# Ethernet.net
KiCad netlist of a schematic drawn in Altium Designer
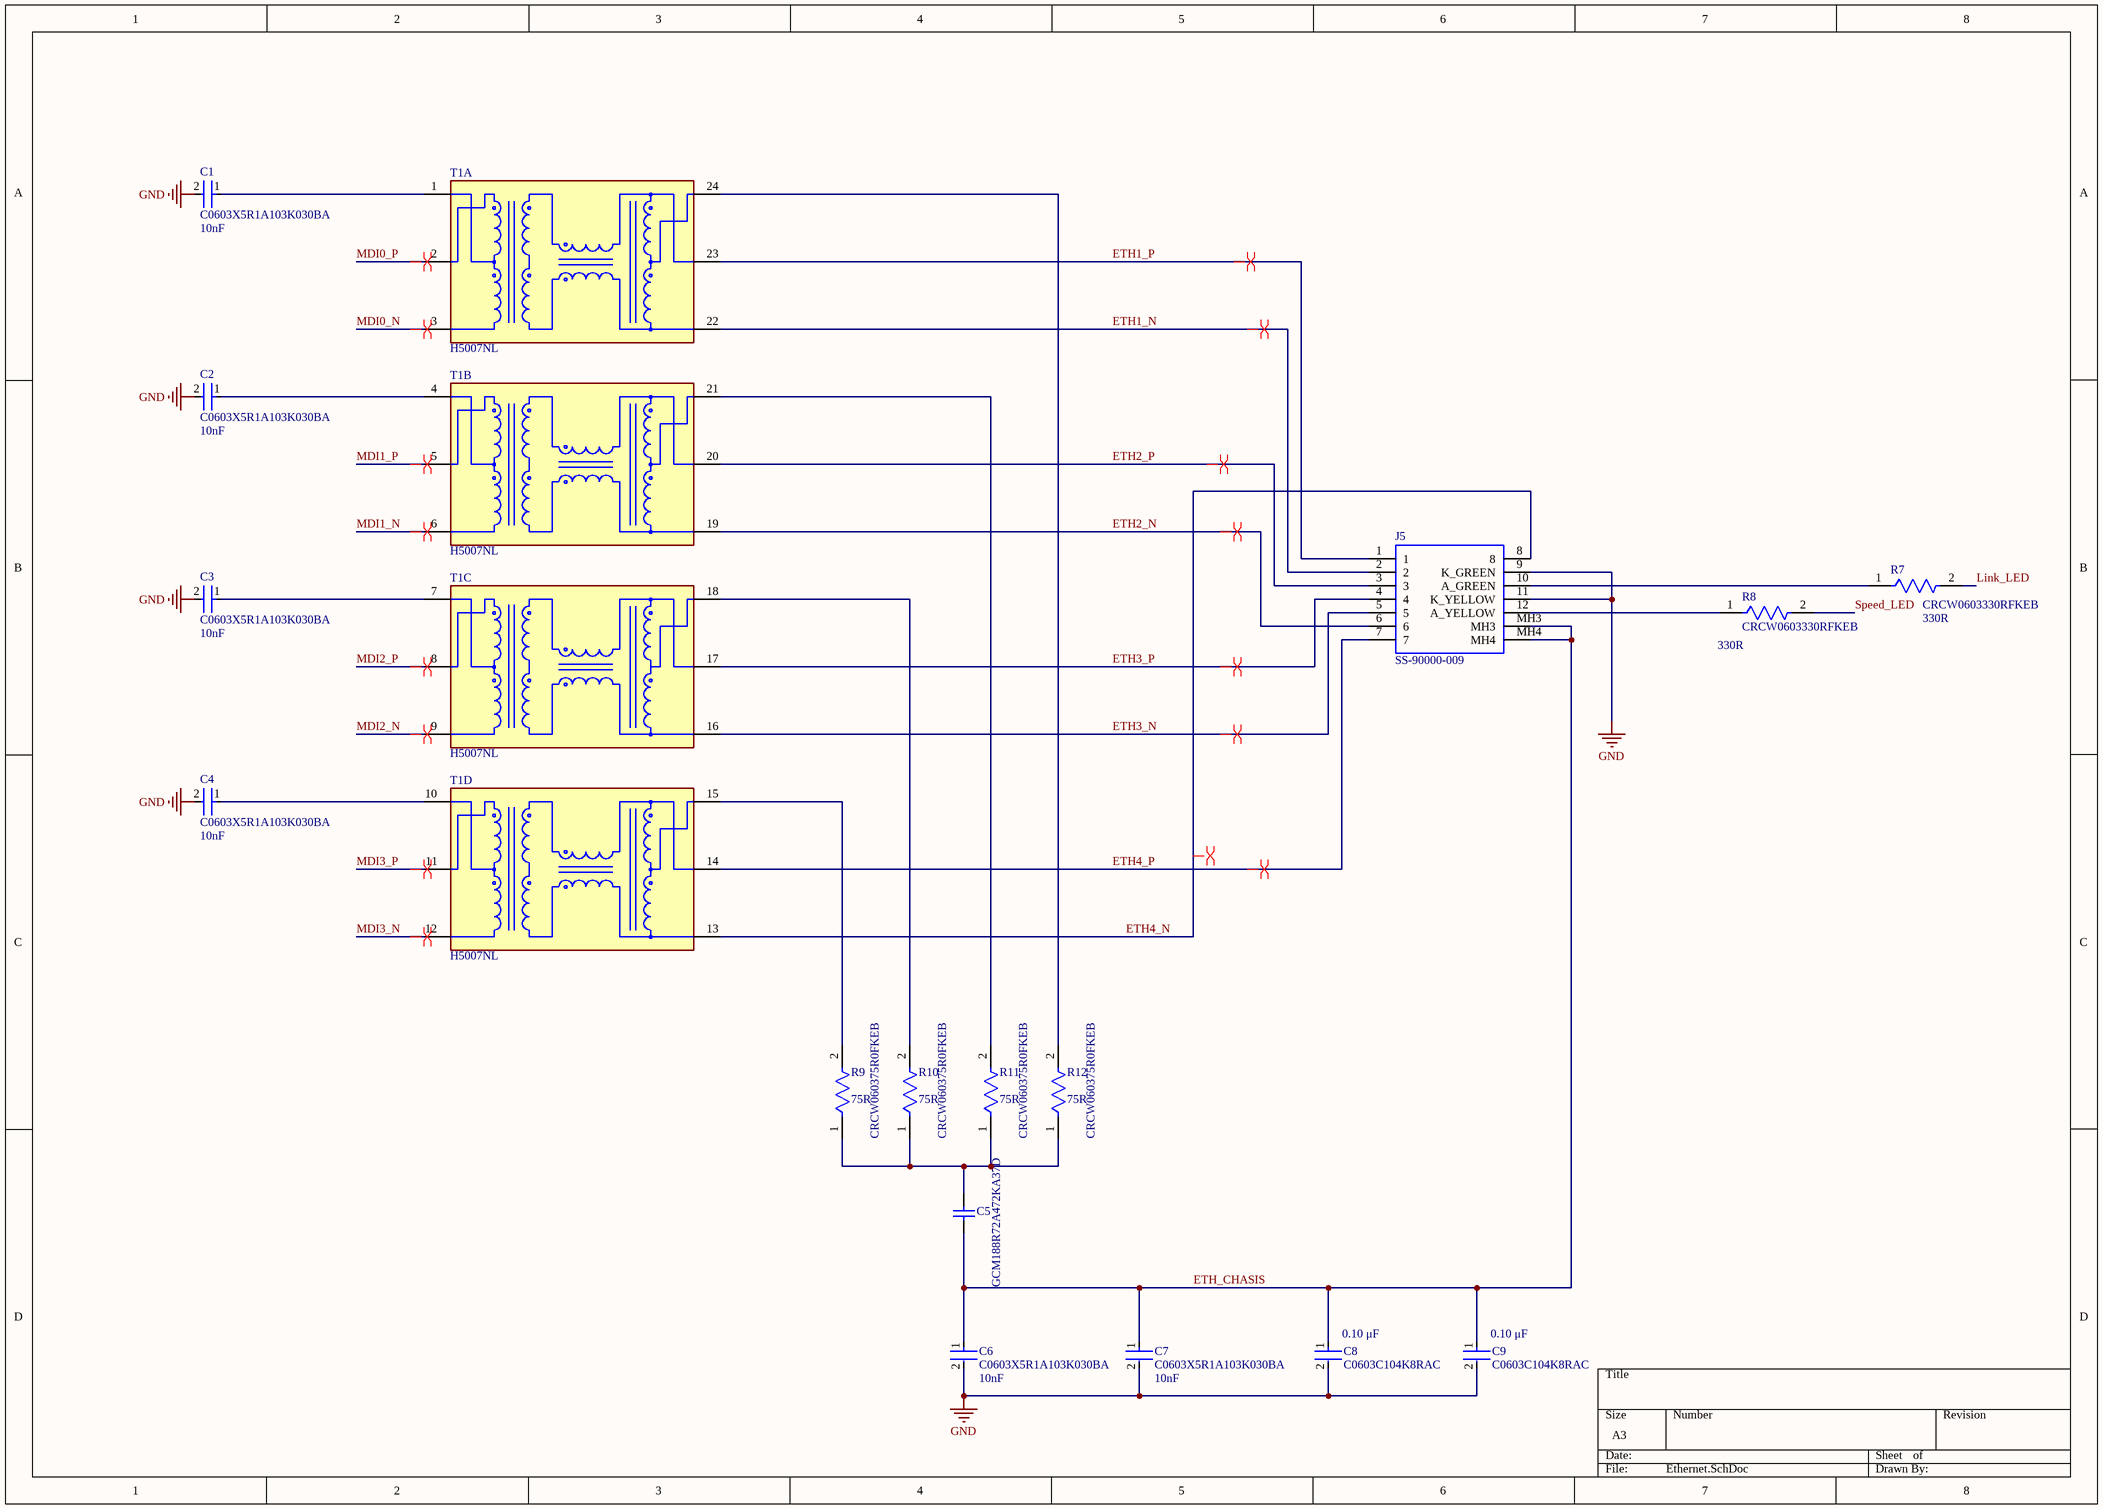
[diagram p0: Ethernet.SchDoc]

(export (version "E")
  (design (tool "Eeschema 10.0.6"))
  (components
    (comp (ref "C1")
      (value "C0603X5R1A103K030BA")
      (footprint "FP-C0603-030-0_03-MFG")
      (description "Multilayer Ceramic Capacitors 10nF ±10% 10V X5R SMD 0201")
      (fields
        (field (name "CAPACITANCE") "10nF")
        (field (name "TOLERANCE") "10%")
        (field (name "VOLTAGE") "10V")
      )
      (libsource (lib "Altium Content Vault") (part "02cd4be3c70576c341d710602a673aa"))
    )
    (comp (ref "C2")
      (value "C0603X5R1A103K030BA")
      (footprint "FP-C0603-030-0_03-MFG")
      (description "Multilayer Ceramic Capacitors 10nF ±10% 10V X5R SMD 0201")
      (fields
        (field (name "CAPACITANCE") "10nF")
        (field (name "TOLERANCE") "10%")
        (field (name "VOLTAGE") "10V")
      )
      (libsource (lib "Altium Content Vault") (part "02cd4be3c70576c341d710602a673aa"))
    )
    (comp (ref "C3")
      (value "C0603X5R1A103K030BA")
      (footprint "FP-C0603-030-0_03-MFG")
      (description "Multilayer Ceramic Capacitors 10nF ±10% 10V X5R SMD 0201")
      (fields
        (field (name "CAPACITANCE") "10nF")
        (field (name "TOLERANCE") "10%")
        (field (name "VOLTAGE") "10V")
      )
      (libsource (lib "Altium Content Vault") (part "02cd4be3c70576c341d710602a673aa"))
    )
    (comp (ref "C4")
      (value "C0603X5R1A103K030BA")
      (footprint "FP-C0603-030-0_03-MFG")
      (description "Multilayer Ceramic Capacitors 10nF ±10% 10V X5R SMD 0201")
      (fields
        (field (name "CAPACITANCE") "10nF")
        (field (name "TOLERANCE") "10%")
        (field (name "VOLTAGE") "10V")
      )
      (libsource (lib "Altium Content Vault") (part "02cd4be3c70576c341d710602a673aa"))
    )
    (comp (ref "C5")
      (value "GCM188R72A472KA37D")
      (footprint "CAPC1608X90X35ML10T15")
      (fields (field (name "MANUFACTURER") "Murata"))
      (libsource (lib "Altium Content Vault") (part "CAP"))
    )
    (comp (ref "C6")
      (value "C0603X5R1A103K030BA")
      (footprint "FP-C0603-030-0_03-MFG")
      (description "Multilayer Ceramic Capacitors 10nF ±10% 10V X5R SMD 0201")
      (fields
        (field (name "CAPACITANCE") "10nF")
        (field (name "TOLERANCE") "10%")
        (field (name "VOLTAGE") "10V")
      )
      (libsource (lib "Altium Content Vault") (part "02cd4be3c70576c341d710602a673aa"))
    )
    (comp (ref "C7")
      (value "C0603X5R1A103K030BA")
      (footprint "FP-C0603-030-0_03-MFG")
      (description "Multilayer Ceramic Capacitors 10nF ±10% 10V X5R SMD 0201")
      (fields
        (field (name "CAPACITANCE") "10nF")
        (field (name "TOLERANCE") "10%")
        (field (name "VOLTAGE") "10V")
      )
      (libsource (lib "Altium Content Vault") (part "02cd4be3c70576c341d710602a673aa"))
    )
    (comp (ref "C8")
      (value "C0603C104K8RAC")
      (footprint "FP-C0603C-CF-MFG")
      (description "C0603 0.10 μF X7R 30ppm/°C 10.00% 10 V")
      (fields
        (field (name "MANUFACTURER") "KEMET")
        (field (name "CAPACITANCE") "0.10 μF")
        (field (name "OCTOPART") "https://octopart.com/c0603c104k8rac-kemet-1325403")
      )
      (libsource (lib "Altium Content Vault") (part "b4654b650e69147ec39a6b967a45e02"))
    )
    (comp (ref "C9")
      (value "C0603C104K8RAC")
      (footprint "FP-C0603C-CF-MFG")
      (description "C0603 0.10 μF X7R 30ppm/°C 10.00% 10 V")
      (fields
        (field (name "MANUFACTURER") "KEMET")
        (field (name "CAPACITANCE") "0.10 μF")
        (field (name "OCTOPART") "https://octopart.com/c0603c104k8rac-kemet-1325403")
      )
      (libsource (lib "Altium Content Vault") (part "b4654b650e69147ec39a6b967a45e02"))
    )
    (comp (ref "J5")
      (value "SS-90000-009")
      (footprint "SS90000009")
      (description "RJ45 8P8C Essential Jack")
      (fields (field (name "MOUSER PART NUMBER") "530-SS-90000-009"))
      (libsource (lib "Schlib2") (part "SS-90000-009"))
    )
    (comp (ref "R7")
      (value "CRCW0603330RFKEB")
      (footprint "FP-CRCW0603-e3-IPC_A")
      (description "RES Thick Film, 330Ω, 1%, 0.1W, 100ppm/°C, 0603")
      (fields (field (name "TOLERANCE") "1%") (field (name "RESISTANCE") "330R"))
      (libsource (lib "Altium Content Vault") (part "1029c3af85768c4190bb7ad29bc67b5"))
    )
    (comp (ref "R8")
      (value "CRCW0603330RFKEB")
      (footprint "FP-CRCW0603-e3-IPC_A")
      (description "RES Thick Film, 330Ω, 1%, 0.1W, 100ppm/°C, 0603")
      (fields (field (name "TOLERANCE") "1%") (field (name "RESISTANCE") "330R"))
      (libsource (lib "Altium Content Vault") (part "1029c3af85768c4190bb7ad29bc67b5"))
    )
    (comp (ref "R9")
      (value "CRCW060375R0FKEB")
      (footprint "FP-CRCW0603-e3-IPC_B")
      (description "RES Thick Film, 75Ω, 1%, 0.1W, 100ppm/°C, 0603")
      (fields (field (name "TOLERANCE") "1%") (field (name "RESISTANCE") "75R"))
      (libsource (lib "Altium Content Vault") (part "1029c3af85768c4190bb7ad29bc67b5"))
    )
    (comp (ref "R10")
      (value "CRCW060375R0FKEB")
      (footprint "FP-CRCW0603-e3-IPC_B")
      (description "RES Thick Film, 75Ω, 1%, 0.1W, 100ppm/°C, 0603")
      (fields (field (name "TOLERANCE") "1%") (field (name "RESISTANCE") "75R"))
      (libsource (lib "Altium Content Vault") (part "1029c3af85768c4190bb7ad29bc67b5"))
    )
    (comp (ref "R11")
      (value "CRCW060375R0FKEB")
      (footprint "FP-CRCW0603-e3-IPC_B")
      (description "RES Thick Film, 75Ω, 1%, 0.1W, 100ppm/°C, 0603")
      (fields (field (name "TOLERANCE") "1%") (field (name "RESISTANCE") "75R"))
      (libsource (lib "Altium Content Vault") (part "1029c3af85768c4190bb7ad29bc67b5"))
    )
    (comp (ref "R12")
      (value "CRCW060375R0FKEB")
      (footprint "FP-CRCW0603-e3-IPC_B")
      (description "RES Thick Film, 75Ω, 1%, 0.1W, 100ppm/°C, 0603")
      (fields (field (name "TOLERANCE") "1%") (field (name "RESISTANCE") "75R"))
      (libsource (lib "Altium Content Vault") (part "1029c3af85768c4190bb7ad29bc67b5"))
    )
    (comp (ref "T1")
      (value "H5007NL")
      (footprint "FP-H5007NL-MFG")
      (description "MODULE SINGLE GIGABIT LAN 24SOIC")
      (libsource (lib "Altium Content Vault") (part "974a45c2ecd5e40aee70eaf68af92de"))
    )
  )
  (nets
    (net (code "1") (name "/ETH1_N") (class "Default")
      (node (ref "J5") (pin "2") (pinfunction "2_2") (pintype "passive"))
      (node (ref "T1") (pin "22") (pinfunction "MX1-_22") (pintype "passive"))
    )
    (net (code "2") (name "/ETH1_P") (class "Default")
      (node (ref "J5") (pin "1") (pinfunction "1_1") (pintype "passive"))
      (node (ref "T1") (pin "23") (pinfunction "MX1+_23") (pintype "passive"))
    )
    (net (code "3") (name "/ETH2_N") (class "Default")
      (node (ref "J5") (pin "6") (pinfunction "6_6") (pintype "passive"))
      (node (ref "T1") (pin "19") (pinfunction "MX2-_19") (pintype "passive"))
    )
    (net (code "4") (name "/ETH2_P") (class "Default")
      (node (ref "J5") (pin "3") (pinfunction "3_3") (pintype "passive"))
      (node (ref "T1") (pin "20") (pinfunction "MX2+_20") (pintype "passive"))
    )
    (net (code "5") (name "/ETH3_N") (class "Default")
      (node (ref "J5") (pin "5") (pinfunction "5_5") (pintype "passive"))
      (node (ref "T1") (pin "16") (pinfunction "MX3-_16") (pintype "passive"))
    )
    (net (code "6") (name "/ETH3_P") (class "Default")
      (node (ref "J5") (pin "4") (pinfunction "4_4") (pintype "passive"))
      (node (ref "T1") (pin "17") (pinfunction "MX3+_17") (pintype "passive"))
    )
    (net (code "7") (name "/ETH4_N") (class "Default")
      (node (ref "J5") (pin "8") (pinfunction "8_8") (pintype "passive"))
      (node (ref "T1") (pin "13") (pinfunction "MX4-_13") (pintype "passive"))
    )
    (net (code "8") (name "/ETH4_P") (class "Default")
      (node (ref "J5") (pin "7") (pinfunction "7_7") (pintype "passive"))
      (node (ref "T1") (pin "14") (pinfunction "MX4+_14") (pintype "passive"))
    )
    (net (code "9") (name "/ETH_CHASIS") (class "Default")
      (node (ref "C5") (pin "1") (pinfunction "1_1") (pintype "passive"))
      (node (ref "C6") (pin "1") (pinfunction "1_1") (pintype "passive"))
      (node (ref "C7") (pin "1") (pinfunction "1_1") (pintype "passive"))
      (node (ref "C8") (pin "1") (pinfunction "1_1") (pintype "passive"))
      (node (ref "C9") (pin "1") (pinfunction "1_1") (pintype "passive"))
      (node (ref "J5") (pin "MH3") (pinfunction "MH3_MH3") (pintype "passive"))
      (node (ref "J5") (pin "MH4") (pinfunction "MH4_MH4") (pintype "passive"))
    )
    (net (code "10") (name "/Link_LED") (class "Default")
      (node (ref "R7") (pin "2") (pinfunction "2_2") (pintype "passive"))
    )
    (net (code "11") (name "/MDI0_N") (class "Default")
      (node (ref "T1") (pin "3") (pinfunction "TD1-_3") (pintype "passive"))
    )
    (net (code "12") (name "/MDI0_P") (class "Default")
      (node (ref "T1") (pin "2") (pinfunction "TD1+_2") (pintype "passive"))
    )
    (net (code "13") (name "/MDI1_N") (class "Default")
      (node (ref "T1") (pin "6") (pinfunction "TD2-_6") (pintype "passive"))
    )
    (net (code "14") (name "/MDI1_P") (class "Default")
      (node (ref "T1") (pin "5") (pinfunction "TD2+_5") (pintype "passive"))
    )
    (net (code "15") (name "/MDI2_N") (class "Default")
      (node (ref "T1") (pin "9") (pinfunction "TD3-_9") (pintype "passive"))
    )
    (net (code "16") (name "/MDI2_P") (class "Default")
      (node (ref "T1") (pin "8") (pinfunction "TD3+_8") (pintype "passive"))
    )
    (net (code "17") (name "/MDI3_N") (class "Default")
      (node (ref "T1") (pin "12") (pinfunction "TD4-_12") (pintype "passive"))
    )
    (net (code "18") (name "/MDI3_P") (class "Default")
      (node (ref "T1") (pin "11") (pinfunction "TD4+_11") (pintype "passive"))
    )
    (net (code "19") (name "/Speed_LED") (class "Default")
      (node (ref "R8") (pin "2") (pinfunction "2_2") (pintype "passive"))
    )
    (net (code "20") (name "GND") (class "Default")
      (node (ref "C1") (pin "2") (pinfunction "2_2") (pintype "passive"))
      (node (ref "C2") (pin "2") (pinfunction "2_2") (pintype "passive"))
      (node (ref "C3") (pin "2") (pinfunction "2_2") (pintype "passive"))
      (node (ref "C4") (pin "2") (pinfunction "2_2") (pintype "passive"))
      (node (ref "C6") (pin "2") (pinfunction "2_2") (pintype "passive"))
      (node (ref "C7") (pin "2") (pinfunction "2_2") (pintype "passive"))
      (node (ref "C8") (pin "2") (pinfunction "2_2") (pintype "passive"))
      (node (ref "C9") (pin "2") (pinfunction "2_2") (pintype "passive"))
      (node (ref "J5") (pin "11") (pinfunction "K_YELLOW_11") (pintype "passive"))
      (node (ref "J5") (pin "9") (pinfunction "K_GREEN_9") (pintype "passive"))
    )
    (net (code "21") (name "Net-(C5-Pad2)") (class "Default")
      (node (ref "C5") (pin "2") (pinfunction "2_2") (pintype "passive"))
      (node (ref "R10") (pin "1") (pinfunction "1_1") (pintype "passive"))
      (node (ref "R11") (pin "1") (pinfunction "1_1") (pintype "passive"))
      (node (ref "R12") (pin "1") (pinfunction "1_1") (pintype "passive"))
      (node (ref "R9") (pin "1") (pinfunction "1_1") (pintype "passive"))
    )
    (net (code "22") (name "Net-(J5-A_GREEN)") (class "Default")
      (node (ref "J5") (pin "10") (pinfunction "A_GREEN_10") (pintype "passive"))
      (node (ref "R7") (pin "1") (pinfunction "1_1") (pintype "passive"))
    )
    (net (code "23") (name "Net-(J5-A_YELLOW)") (class "Default")
      (node (ref "J5") (pin "12") (pinfunction "A_YELLOW_12") (pintype "passive"))
      (node (ref "R8") (pin "1") (pinfunction "1_1") (pintype "passive"))
    )
    (net (code "24") (name "Net-(T1A-MCT1)") (class "Default")
      (node (ref "R12") (pin "2") (pinfunction "2_2") (pintype "passive"))
      (node (ref "T1") (pin "24") (pinfunction "MCT1_24") (pintype "passive"))
    )
    (net (code "25") (name "Net-(T1A-TCT1)") (class "Default")
      (node (ref "C1") (pin "1") (pinfunction "1_1") (pintype "passive"))
      (node (ref "T1") (pin "1") (pinfunction "TCT1_1") (pintype "passive"))
    )
    (net (code "26") (name "Net-(T1B-MCT2)") (class "Default")
      (node (ref "R11") (pin "2") (pinfunction "2_2") (pintype "passive"))
      (node (ref "T1") (pin "21") (pinfunction "MCT2_21") (pintype "passive"))
    )
    (net (code "27") (name "Net-(T1B-TCT2)") (class "Default")
      (node (ref "C2") (pin "1") (pinfunction "1_1") (pintype "passive"))
      (node (ref "T1") (pin "4") (pinfunction "TCT2_4") (pintype "passive"))
    )
    (net (code "28") (name "Net-(T1C-MCT3)") (class "Default")
      (node (ref "R10") (pin "2") (pinfunction "2_2") (pintype "passive"))
      (node (ref "T1") (pin "18") (pinfunction "MCT3_18") (pintype "passive"))
    )
    (net (code "29") (name "Net-(T1C-TCT3)") (class "Default")
      (node (ref "C3") (pin "1") (pinfunction "1_1") (pintype "passive"))
      (node (ref "T1") (pin "7") (pinfunction "TCT3_7") (pintype "passive"))
    )
    (net (code "30") (name "Net-(T1D-MCT4)") (class "Default")
      (node (ref "R9") (pin "2") (pinfunction "2_2") (pintype "passive"))
      (node (ref "T1") (pin "15") (pinfunction "MCT4_15") (pintype "passive"))
    )
    (net (code "31") (name "Net-(T1D-TCT4)") (class "Default")
      (node (ref "C4") (pin "1") (pinfunction "1_1") (pintype "passive"))
      (node (ref "T1") (pin "10") (pinfunction "TCT4_10") (pintype "passive"))
    )
  )
)
